# Quad-Stage-Prototype_LED_V1_0.net
KiCad netlist of a schematic drawn in Altium Designer
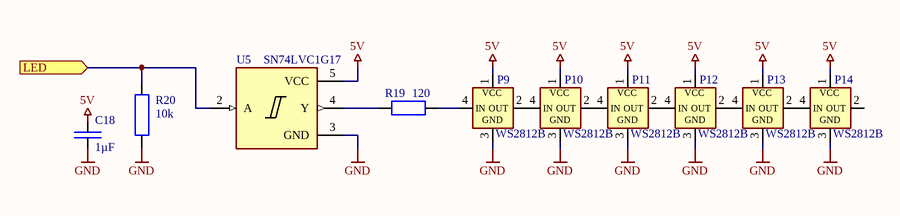
[diagram p0: Quad-Stage-Prototype_LED_V1.0.SchDoc]

(export (version "E")
  (design (tool "Eeschema 10.0.6"))
  (components
    (comp (ref "C18")
      (value "1µF")
      (footprint "SMD Keramikkondensator 0603")
      (description "CAP-MK")
      (libsource (lib "AudioAmp") (part "C-CAPACITOR"))
    )
    (comp (ref "P9")
      (value "WS2812B")
      (footprint "SMD LED WS2812B-5050")
      (description "Smart RGB-LED")
      (libsource (lib "Quad-Stage-Prototype") (part "P-WS2812B"))
    )
    (comp (ref "P10")
      (value "WS2812B")
      (footprint "SMD LED WS2812B-5050")
      (description "Smart RGB-LED")
      (libsource (lib "Quad-Stage-Prototype") (part "P-WS2812B"))
    )
    (comp (ref "P11")
      (value "WS2812B")
      (footprint "SMD LED WS2812B-5050")
      (description "Smart RGB-LED")
      (libsource (lib "Quad-Stage-Prototype") (part "P-WS2812B"))
    )
    (comp (ref "P12")
      (value "WS2812B")
      (footprint "SMD LED WS2812B-5050")
      (description "Smart RGB-LED")
      (libsource (lib "Quad-Stage-Prototype") (part "P-WS2812B"))
    )
    (comp (ref "P13")
      (value "WS2812B")
      (footprint "SMD LED WS2812B-5050")
      (description "Smart RGB-LED")
      (libsource (lib "Quad-Stage-Prototype") (part "P-WS2812B"))
    )
    (comp (ref "P14")
      (value "WS2812B")
      (footprint "SMD LED WS2812B-5050")
      (description "Smart RGB-LED")
      (libsource (lib "Quad-Stage-Prototype") (part "P-WS2812B"))
    )
    (comp (ref "R19")
      (value "120")
      (footprint "SMD Widerstand 0603")
      (description "SMD Chip Resistor E24")
      (libsource (lib "Fleet-Monitor") (part "E24 - 120"))
    )
    (comp (ref "R20")
      (value "10k")
      (footprint "SMD Widerstand 0603")
      (description "RES (E=Heizwiderstand B=Messwandler)")
      (libsource (lib "TFS Integrated Library") (part "R-RESISTOR"))
    )
    (comp (ref "U5")
      (value "SN74LVC1G17")
      (footprint "SMD IC SOT-363 (SC-70-5)")
      (description "Single Schmitt-Trigger Buffer")
      (libsource (lib "Quad-Stage-Prototype") (part "U-SN74LVC1G17-Q1"))
    )
  )
  (nets
    (net (code "1") (name "/LED") (class "Default")
      (node (ref "R20") (pin "2") (pinfunction "2_2") (pintype "passive"))
      (node (ref "U5") (pin "2") (pinfunction "A_2") (pintype "input"))
    )
    (net (code "2") (name "5V") (class "Default")
      (node (ref "C18") (pin "2") (pinfunction "2_2") (pintype "passive"))
      (node (ref "P10") (pin "1") (pinfunction "VCC_1") (pintype "power_in"))
      (node (ref "P11") (pin "1") (pinfunction "VCC_1") (pintype "power_in"))
      (node (ref "P12") (pin "1") (pinfunction "VCC_1") (pintype "power_in"))
      (node (ref "P13") (pin "1") (pinfunction "VCC_1") (pintype "power_in"))
      (node (ref "P14") (pin "1") (pinfunction "VCC_1") (pintype "power_in"))
      (node (ref "P9") (pin "1") (pinfunction "VCC_1") (pintype "power_in"))
      (node (ref "U5") (pin "5") (pinfunction "VCC_5") (pintype "power_in"))
    )
    (net (code "3") (name "GND") (class "Default")
      (node (ref "C18") (pin "1") (pinfunction "1_1") (pintype "passive"))
      (node (ref "P10") (pin "3") (pinfunction "GND_3") (pintype "power_in"))
      (node (ref "P11") (pin "3") (pinfunction "GND_3") (pintype "power_in"))
      (node (ref "P12") (pin "3") (pinfunction "GND_3") (pintype "power_in"))
      (node (ref "P13") (pin "3") (pinfunction "GND_3") (pintype "power_in"))
      (node (ref "P14") (pin "3") (pinfunction "GND_3") (pintype "power_in"))
      (node (ref "P9") (pin "3") (pinfunction "GND_3") (pintype "power_in"))
      (node (ref "R20") (pin "1") (pinfunction "1_1") (pintype "passive"))
      (node (ref "U5") (pin "3") (pinfunction "GND_3") (pintype "power_in"))
    )
    (net (code "4") (name "Net-(P9-IN)") (class "Default")
      (node (ref "P9") (pin "4") (pinfunction "IN_4") (pintype "power_in"))
      (node (ref "R19") (pin "1") (pinfunction "1_1") (pintype "passive"))
    )
    (net (code "5") (name "Net-(P10-IN)") (class "Default")
      (node (ref "P10") (pin "4") (pinfunction "IN_4") (pintype "power_in"))
      (node (ref "P9") (pin "2") (pinfunction "OUT_2") (pintype "power_in"))
    )
    (net (code "6") (name "Net-(P10-OUT)") (class "Default")
      (node (ref "P10") (pin "2") (pinfunction "OUT_2") (pintype "power_in"))
      (node (ref "P11") (pin "4") (pinfunction "IN_4") (pintype "power_in"))
    )
    (net (code "7") (name "Net-(P11-OUT)") (class "Default")
      (node (ref "P11") (pin "2") (pinfunction "OUT_2") (pintype "power_in"))
      (node (ref "P12") (pin "4") (pinfunction "IN_4") (pintype "power_in"))
    )
    (net (code "8") (name "Net-(P12-OUT)") (class "Default")
      (node (ref "P12") (pin "2") (pinfunction "OUT_2") (pintype "power_in"))
      (node (ref "P13") (pin "4") (pinfunction "IN_4") (pintype "power_in"))
    )
    (net (code "9") (name "Net-(P13-OUT)") (class "Default")
      (node (ref "P13") (pin "2") (pinfunction "OUT_2") (pintype "power_in"))
      (node (ref "P14") (pin "4") (pinfunction "IN_4") (pintype "power_in"))
    )
    (net (code "10") (name "Net-(U5-Y)") (class "Default")
      (node (ref "R19") (pin "2") (pinfunction "2_2") (pintype "passive"))
      (node (ref "U5") (pin "4") (pinfunction "Y_4") (pintype "output"))
    )
    (net (code "11") (name "unconnected-(P14-OUT-Pad2)") (class "Default")
      (node (ref "P14") (pin "2") (pinfunction "OUT_2") (pintype "power_in"))
    )
    (net (code "12") (name "unconnected-(U5-NC-Pad1)") (class "Default")
      (node (ref "U5") (pin "1") (pinfunction "NC_1") (pintype "passive"))
    )
  )
)
